# B302_PI_Coil_Driver.net
KiCad netlist of a schematic drawn in Altium Designer
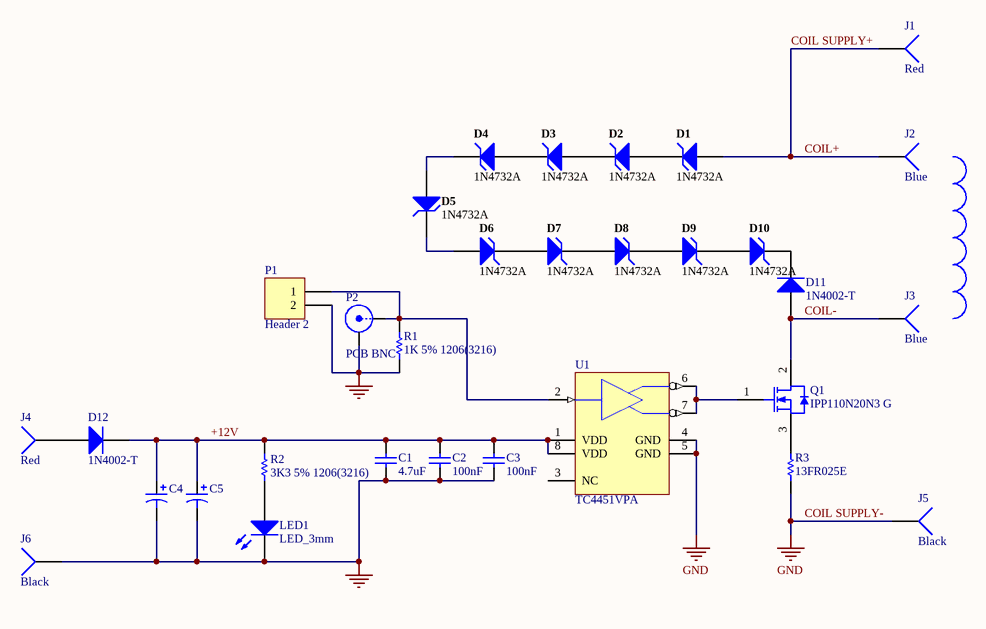
[diagram p0: B302 PI Coil Driver.SchDoc]

(export (version "E")
  (design (tool "Eeschema 10.0.6"))
  (components
    (comp (ref "C1")
      (value "4.7uF")
      (footprint "CAPC1206(3216)190_N")
      (description "CAP 4.7uF 50V ±10% 1206 (3216 Metric) Thickness 1.9mm SMD")
      (fields (field (name "TOLERANCE") "Â±10%"))
      (libsource (lib "Altium Content Vault") (part "CAP"))
    )
    (comp (ref "C2")
      (value "100nF")
      (footprint "CAPC1206(3216)150_M")
      (description "CAP 100nF 100V ±20% 1206 (3216 Metric) Thickness 1.45mm SMD")
      (fields (field (name "TOLERANCE") "Â±20%"))
      (libsource (lib "Altium Content Vault") (part "CAP"))
    )
    (comp (ref "C3")
      (value "100nF")
      (footprint "CAPC1206(3216)150_M")
      (description "CAP 100nF 100V ±20% 1206 (3216 Metric) Thickness 1.45mm SMD")
      (fields (field (name "TOLERANCE") "Â±20%"))
      (libsource (lib "Altium Content Vault") (part "CAP"))
    )
    (comp (ref "C4")
      (value "Cap Polarised")
      (footprint "Vishay Roederstein Electrolytic Radial-Lead Capacitor:CAPPR5-10X12.5")
      (libsource (lib "Matt SCH Library") (part "Cap Polarised"))
    )
    (comp (ref "C5")
      (value "ECA-1HM470")
      (footprint "PNSC-ECA-1HM470")
      (description "CAP ALUM 47UF 50V 20% RADIAL")
      (libsource (lib "Altium Content Vault") (part "CMP-1665-00013-1"))
    )
    (comp (ref "D1")
      (value "1N4732A")
      (footprint "FAIR-DO-41-2_V")
      (description "Zener Diode, 4.7V, 1W, 5%, -65 to 200 degC, 2-Pin DO-41, Body 2.72 x 5.2 mm, RoHS")
      (fields (field (name "TOLERANCE") "5%") (field (name "MANUFACTURER") "Fairchild Semiconductor"))
      (libsource (lib "Altium Content Vault") (part "CMP-0892-00030-1"))
    )
    (comp (ref "D2")
      (value "1N4732A")
      (footprint "FAIR-DO-41-2_V")
      (description "Zener Diode, 4.7V, 1W, 5%, -65 to 200 degC, 2-Pin DO-41, Body 2.72 x 5.2 mm, RoHS")
      (fields (field (name "TOLERANCE") "5%") (field (name "MANUFACTURER") "Fairchild Semiconductor"))
      (libsource (lib "Altium Content Vault") (part "CMP-0892-00030-1"))
    )
    (comp (ref "D3")
      (value "1N4732A")
      (footprint "FAIR-DO-41-2_V")
      (description "Zener Diode, 4.7V, 1W, 5%, -65 to 200 degC, 2-Pin DO-41, Body 2.72 x 5.2 mm, RoHS")
      (fields (field (name "TOLERANCE") "5%") (field (name "MANUFACTURER") "Fairchild Semiconductor"))
      (libsource (lib "Altium Content Vault") (part "CMP-0892-00030-1"))
    )
    (comp (ref "D4")
      (value "1N4732A")
      (footprint "FAIR-DO-41-2_V")
      (description "Zener Diode, 4.7V, 1W, 5%, -65 to 200 degC, 2-Pin DO-41, Body 2.72 x 5.2 mm, RoHS")
      (fields (field (name "TOLERANCE") "5%") (field (name "MANUFACTURER") "Fairchild Semiconductor"))
      (libsource (lib "Altium Content Vault") (part "CMP-0892-00030-1"))
    )
    (comp (ref "D5")
      (value "1N4732A")
      (footprint "FAIR-DO-41-2_V")
      (description "Zener Diode, 4.7V, 1W, 5%, -65 to 200 degC, 2-Pin DO-41, Body 2.72 x 5.2 mm, RoHS")
      (fields (field (name "TOLERANCE") "5%") (field (name "MANUFACTURER") "Fairchild Semiconductor"))
      (libsource (lib "Altium Content Vault") (part "FAIR-DZEN-A1K2-2"))
    )
    (comp (ref "D6")
      (value "1N4732A")
      (footprint "FAIR-DO-41-2_V")
      (description "Zener Diode, 4.7V, 1W, 5%, -65 to 200 degC, 2-Pin DO-41, Body 2.72 x 5.2 mm, RoHS")
      (fields (field (name "TOLERANCE") "5%") (field (name "MANUFACTURER") "Fairchild Semiconductor"))
      (libsource (lib "Altium Content Vault") (part "FAIR-DZEN-A1K2-2"))
    )
    (comp (ref "D7")
      (value "1N4732A")
      (footprint "FAIR-DO-41-2_V")
      (description "Zener Diode, 4.7V, 1W, 5%, -65 to 200 degC, 2-Pin DO-41, Body 2.72 x 5.2 mm, RoHS")
      (fields (field (name "TOLERANCE") "5%") (field (name "MANUFACTURER") "Fairchild Semiconductor"))
      (libsource (lib "Altium Content Vault") (part "FAIR-DZEN-A1K2-2"))
    )
    (comp (ref "D8")
      (value "1N4732A")
      (footprint "FAIR-DO-41-2_V")
      (description "Zener Diode, 4.7V, 1W, 5%, -65 to 200 degC, 2-Pin DO-41, Body 2.72 x 5.2 mm, RoHS")
      (fields (field (name "TOLERANCE") "5%") (field (name "MANUFACTURER") "Fairchild Semiconductor"))
      (libsource (lib "Altium Content Vault") (part "FAIR-DZEN-A1K2-2"))
    )
    (comp (ref "D9")
      (value "1N4732A")
      (footprint "FAIR-DO-41-2_V")
      (description "Zener Diode, 4.7V, 1W, 5%, -65 to 200 degC, 2-Pin DO-41, Body 2.72 x 5.2 mm, RoHS")
      (fields (field (name "TOLERANCE") "5%") (field (name "MANUFACTURER") "Fairchild Semiconductor"))
      (libsource (lib "Altium Content Vault") (part "FAIR-DZEN-A1K2-2"))
    )
    (comp (ref "D10")
      (value "1N4732A")
      (footprint "FAIR-DO-41-2_V")
      (description "Zener Diode, 4.7V, 1W, 5%, -65 to 200 degC, 2-Pin DO-41, Body 2.72 x 5.2 mm, RoHS")
      (fields (field (name "TOLERANCE") "5%") (field (name "MANUFACTURER") "Fairchild Semiconductor"))
      (libsource (lib "Altium Content Vault") (part "FAIR-DZEN-A1K2-2"))
    )
    (comp (ref "D11")
      (value "1N4002-T")
      (footprint "DIOD-DO-41-P-2_V")
      (description "1.0 A Rectifier, 15 pF, 100 V, -65 to 150 degC, 2-Pin DO-41 Plastic, RoHS, Tape and Reel")
      (fields (field (name "MANUFACTURER") "Diodes Inc"))
      (libsource (lib "Altium Content Vault") (part "DIOD-D-A1K2-2"))
    )
    (comp (ref "D12")
      (value "1N4002-T")
      (footprint "DIOD-DO-41-P-2_V")
      (description "1.0 A Rectifier, 15 pF, 100 V, -65 to 150 degC, 2-Pin DO-41 Plastic, RoHS, Tape and Reel")
      (fields (field (name "MANUFACTURER") "Diodes Inc"))
      (libsource (lib "Altium Content Vault") (part "DIOD-D-A1K2-2"))
    )
    (comp (ref "J1")
      (value "Red")
      (footprint "Matt PCB Library:4mm socket right angled")
      (libsource (lib "Matt SCH Library") (part "4mm pcb socket r/a red"))
    )
    (comp (ref "J2")
      (value "Blue")
      (footprint "Matt PCB Library:4mm socket right angled")
      (libsource (lib "Matt SCH Library") (part "4mm pcb socket r/a blue"))
    )
    (comp (ref "J3")
      (value "Blue")
      (footprint "Matt PCB Library:4mm socket right angled")
      (libsource (lib "Matt SCH Library") (part "4mm pcb socket r/a blue"))
    )
    (comp (ref "J4")
      (value "Red")
      (footprint "Matt PCB Library:4mm socket right angled")
      (libsource (lib "Matt SCH Library") (part "4mm pcb socket r/a red"))
    )
    (comp (ref "J5")
      (value "Black")
      (footprint "Matt PCB Library:4mm socket right angled")
      (libsource (lib "Matt SCH Library") (part "4mm pcb socket r/a black"))
    )
    (comp (ref "J6")
      (value "Black")
      (footprint "Matt PCB Library:4mm socket right angled")
      (libsource (lib "Matt SCH Library") (part "4mm pcb socket r/a black"))
    )
    (comp (ref "LED1")
      (value "LED_3mm")
      (footprint "LED-Polarized - 3mm")
      (description "3mm LED")
      (fields (field (name "PUBLISHER") "Altium Limited"))
      (libsource (lib "Matt SCH Library") (part "LED_3mm"))
    )
    (comp (ref "P1")
      (value "Header 2")
      (footprint "HDR1X2")
      (description "Header, 2-Pin")
      (fields (field (name "PUBLISHER") "Altium Limited"))
      (libsource (lib "Miscellaneous Connectors") (part "Header 2"))
    )
    (comp (ref "P2")
      (value "PCB BNC")
      (footprint "Matt PCB Library:PCB BNC RA Socket")
      (description "PCB RA BNC Socket")
      (libsource (lib "Matt SCH Library") (part "PCB BNC"))
    )
    (comp (ref "Q1")
      (value "IPP110N20N3 G")
      (footprint "INF-PG-TO220-3-1_A_V")
      (fields (field (name "MANUFACTURER") "Infineon"))
      (libsource (lib "Altium Content Vault") (part "INF-NEMOS-GDS-3"))
    )
    (comp (ref "R1")
      (value "1K 5% 1206(3216)")
      (footprint "RESC1206(3216)_N")
      (description "1K 0.25W 5% 1206 (3216 Metric)  SMD")
      (fields
        (field (name "TOLERANCE") "5 %")
        (field (name "POWER") "0.25 W")
        (field (name "PUBLISHER") "Altium Limited")
      )
      (libsource (lib "Altium Content Vault") (part "RES"))
    )
    (comp (ref "R2")
      (value "3K3 5% 1206(3216)")
      (footprint "RESC1206(3216)_N")
      (description "3K3 0.25W 5% 1206 (3216 Metric)  SMD")
      (fields
        (field (name "POWER") "0.25 W")
        (field (name "TOLERANCE") "5 %")
        (field (name "PUBLISHER") "Altium Limited")
      )
      (libsource (lib "Altium Content Vault") (part "RES"))
    )
    (comp (ref "R3")
      (value "13FR025E")
      (footprint "OMTE-13FR025E")
      (description "RES CURRENT SENSE .025 OHM 3W")
      (fields (field (name "MANUFACTURER") "Ohmite"))
      (libsource (lib "Altium Content Vault") (part "CMP-1678-00001-4"))
    )
    (comp (ref "U1")
      (value "TC4451VPA")
      (footprint "PDIP300-PA8")
      (description "12A High-Speed MOSFET Drivers, Inverting, Extended Temperature")
      (libsource (lib "Altium Content Vault") (part "IN-MOSDRV-TC1410-8"))
    )
  )
  (nets
    (net (code "1") (name "/+12V") (class "Default")
      (node (ref "C1") (pin "1") (pinfunction "1_1") (pintype "passive"))
      (node (ref "C2") (pin "1") (pinfunction "1_1") (pintype "passive"))
      (node (ref "C3") (pin "1") (pinfunction "1_1") (pintype "passive"))
      (node (ref "C4") (pin "1") (pinfunction "1_1") (pintype "passive"))
      (node (ref "C5") (pin "1") (pinfunction "+_1") (pintype "passive"))
      (node (ref "D12") (pin "2") (pinfunction "K_2") (pintype "passive"))
      (node (ref "R2") (pin "2") (pinfunction "2_2") (pintype "passive"))
      (node (ref "U1") (pin "1") (pinfunction "VDD_1") (pintype "power_in"))
      (node (ref "U1") (pin "8") (pinfunction "VDD_8") (pintype "power_in"))
    )
    (net (code "2") (name "/COIL SUPPLY+") (class "Default")
      (node (ref "D1") (pin "1") (pinfunction "A_1") (pintype "passive"))
      (node (ref "J1") (pin "1") (pinfunction "1_1") (pintype "passive"))
      (node (ref "J2") (pin "1") (pinfunction "1_1") (pintype "passive"))
    )
    (net (code "3") (name "/COIL-") (class "Default")
      (node (ref "D11") (pin "1") (pinfunction "A_1") (pintype "passive"))
      (node (ref "J3") (pin "1") (pinfunction "1_1") (pintype "passive"))
      (node (ref "Q1") (pin "2") (pinfunction "DRAIN_2") (pintype "passive"))
    )
    (net (code "4") (name "GND") (class "Default")
      (node (ref "C1") (pin "2") (pinfunction "2_2") (pintype "passive"))
      (node (ref "C2") (pin "2") (pinfunction "2_2") (pintype "passive"))
      (node (ref "C3") (pin "2") (pinfunction "2_2") (pintype "passive"))
      (node (ref "C4") (pin "2") (pinfunction "2_2") (pintype "passive"))
      (node (ref "C5") (pin "2") (pinfunction "-_2") (pintype "passive"))
      (node (ref "J5") (pin "1") (pinfunction "1_1") (pintype "passive"))
      (node (ref "J6") (pin "1") (pinfunction "1_1") (pintype "passive"))
      (node (ref "LED1") (pin "K") (pinfunction "K_K") (pintype "passive"))
      (node (ref "P1") (pin "2") (pinfunction "2_2") (pintype "passive"))
      (node (ref "P2") (pin "2") (pinfunction "Y_2") (pintype "passive"))
      (node (ref "R1") (pin "1") (pinfunction "1_1") (pintype "passive"))
      (node (ref "R3") (pin "1") (pinfunction "1_1") (pintype "passive"))
      (node (ref "U1") (pin "4") (pinfunction "GND_4") (pintype "power_in"))
      (node (ref "U1") (pin "5") (pinfunction "GND_5") (pintype "power_in"))
    )
    (net (code "5") (name "Net-(D1-K)") (class "Default")
      (node (ref "D1") (pin "2") (pinfunction "K_2") (pintype "passive"))
      (node (ref "D2") (pin "1") (pinfunction "A_1") (pintype "passive"))
    )
    (net (code "6") (name "Net-(D2-K)") (class "Default")
      (node (ref "D2") (pin "2") (pinfunction "K_2") (pintype "passive"))
      (node (ref "D3") (pin "1") (pinfunction "A_1") (pintype "passive"))
    )
    (net (code "7") (name "Net-(D3-K)") (class "Default")
      (node (ref "D3") (pin "2") (pinfunction "K_2") (pintype "passive"))
      (node (ref "D4") (pin "1") (pinfunction "A_1") (pintype "passive"))
    )
    (net (code "8") (name "Net-(D4-K)") (class "Default")
      (node (ref "D4") (pin "2") (pinfunction "K_2") (pintype "passive"))
      (node (ref "D5") (pin "1") (pinfunction "A_1") (pintype "passive"))
    )
    (net (code "9") (name "Net-(D5-K)") (class "Default")
      (node (ref "D5") (pin "2") (pinfunction "K_2") (pintype "passive"))
      (node (ref "D6") (pin "1") (pinfunction "A_1") (pintype "passive"))
    )
    (net (code "10") (name "Net-(D6-K)") (class "Default")
      (node (ref "D6") (pin "2") (pinfunction "K_2") (pintype "passive"))
      (node (ref "D7") (pin "1") (pinfunction "A_1") (pintype "passive"))
    )
    (net (code "11") (name "Net-(D7-K)") (class "Default")
      (node (ref "D7") (pin "2") (pinfunction "K_2") (pintype "passive"))
      (node (ref "D8") (pin "1") (pinfunction "A_1") (pintype "passive"))
    )
    (net (code "12") (name "Net-(D8-K)") (class "Default")
      (node (ref "D8") (pin "2") (pinfunction "K_2") (pintype "passive"))
      (node (ref "D9") (pin "1") (pinfunction "A_1") (pintype "passive"))
    )
    (net (code "13") (name "Net-(D10-A)") (class "Default")
      (node (ref "D10") (pin "1") (pinfunction "A_1") (pintype "passive"))
      (node (ref "D9") (pin "2") (pinfunction "K_2") (pintype "passive"))
    )
    (net (code "14") (name "Net-(D10-K)") (class "Default")
      (node (ref "D10") (pin "2") (pinfunction "K_2") (pintype "passive"))
      (node (ref "D11") (pin "2") (pinfunction "K_2") (pintype "passive"))
    )
    (net (code "15") (name "Net-(D12-A)") (class "Default")
      (node (ref "D12") (pin "1") (pinfunction "A_1") (pintype "passive"))
      (node (ref "J4") (pin "1") (pinfunction "1_1") (pintype "passive"))
    )
    (net (code "16") (name "Net-(LED1-PadA)") (class "Default")
      (node (ref "LED1") (pin "A") (pinfunction "A_A") (pintype "passive"))
      (node (ref "R2") (pin "1") (pinfunction "1_1") (pintype "passive"))
    )
    (net (code "17") (name "Net-(P2-X)") (class "Default")
      (node (ref "P1") (pin "1") (pinfunction "1_1") (pintype "passive"))
      (node (ref "P2") (pin "1") (pinfunction "X_1") (pintype "passive"))
      (node (ref "R1") (pin "2") (pinfunction "2_2") (pintype "passive"))
      (node (ref "U1") (pin "2") (pinfunction "IN_2") (pintype "input"))
    )
    (net (code "18") (name "Net-(Q1-GATE)") (class "Default")
      (node (ref "Q1") (pin "1") (pinfunction "GATE_1") (pintype "passive"))
      (node (ref "U1") (pin "6") (pinfunction "~{OUT}_6") (pintype "output"))
      (node (ref "U1") (pin "7") (pinfunction "~{OUT}_7") (pintype "output"))
    )
    (net (code "19") (name "Net-(Q1-SOURCE)") (class "Default")
      (node (ref "Q1") (pin "3") (pinfunction "SOURCE_3") (pintype "passive"))
      (node (ref "R3") (pin "2") (pinfunction "2_2") (pintype "passive"))
    )
    (net (code "20") (name "unconnected-(U1-NC-Pad3)") (class "Default")
      (node (ref "U1") (pin "3") (pinfunction "NC_3") (pintype "passive"))
    )
  )
)
